# attinytrafficlight.net
KiCad netlist of a schematic drawn in EAGLE
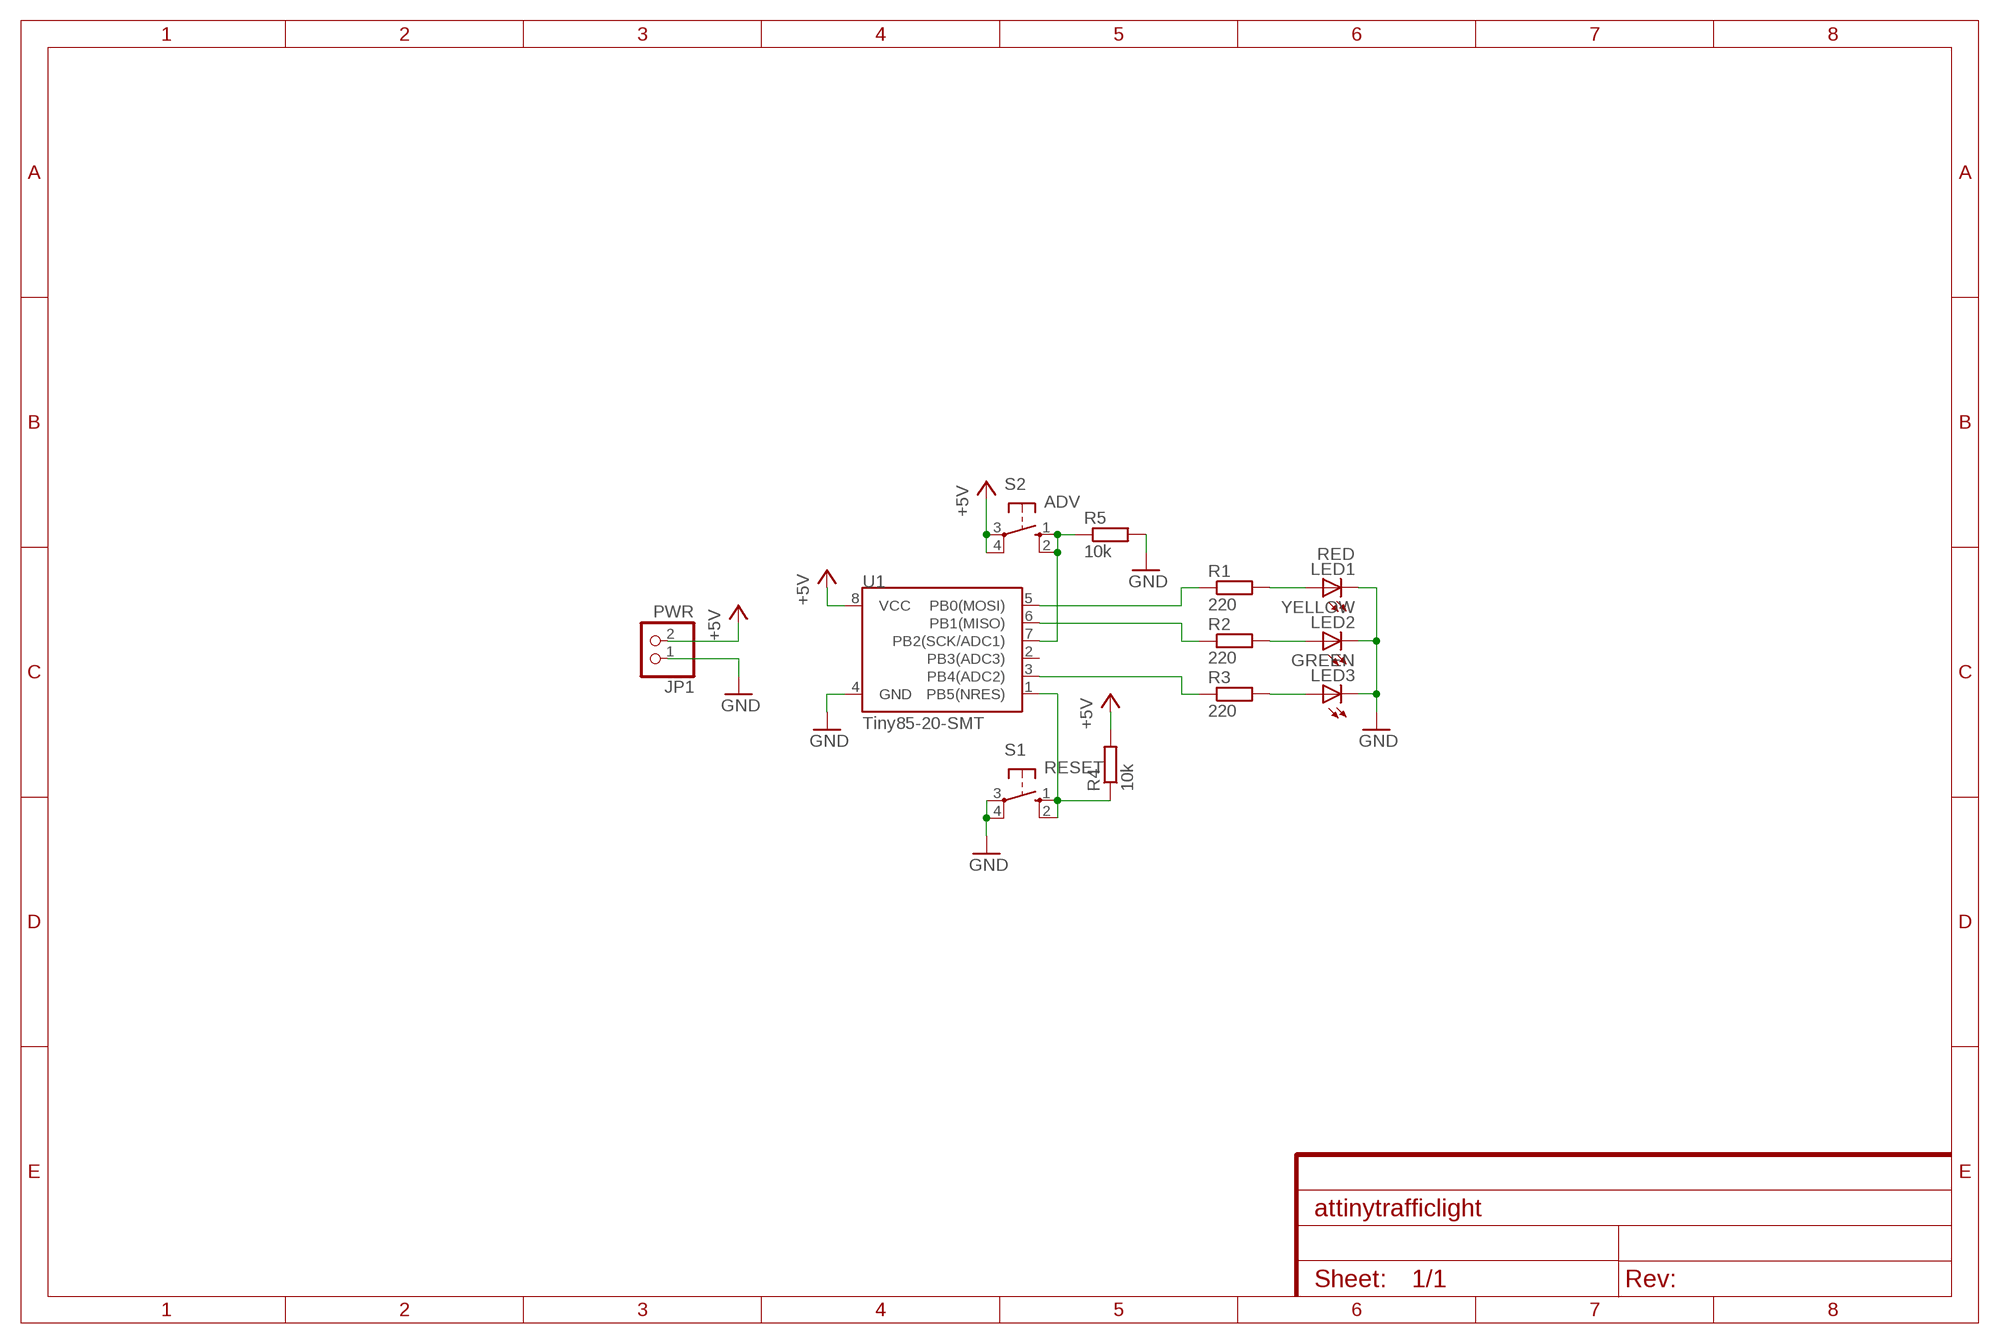
[diagram p0: schematic, sheet 1]

(export (version "E")
  (design (tool "Eeschema 10.0.6"))
  (components
    (comp (ref "JP1")
      (value "PWR")
      (footprint "eagle-import:1X02")
      (libsource (lib "eagle-import") (part "PINHD-1X2"))
    )
    (comp (ref "LED1")
      (value "RED")
      (footprint "eagle-import:SML0805")
      (libsource (lib "eagle-import") (part "LEDSML0805"))
    )
    (comp (ref "LED2")
      (value "YELLOW")
      (footprint "eagle-import:SML0805")
      (libsource (lib "eagle-import") (part "LEDSML0805"))
    )
    (comp (ref "LED3")
      (value "GREEN")
      (footprint "eagle-import:SML0805")
      (libsource (lib "eagle-import") (part "LEDSML0805"))
    )
    (comp (ref "R1")
      (value "220")
      (footprint "eagle-import:R0805")
      (libsource (lib "eagle-import") (part "R-EU_R0805"))
    )
    (comp (ref "R2")
      (value "220")
      (footprint "eagle-import:R0805")
      (libsource (lib "eagle-import") (part "R-EU_R0805"))
    )
    (comp (ref "R3")
      (value "220")
      (footprint "eagle-import:R0805")
      (libsource (lib "eagle-import") (part "R-EU_R0805"))
    )
    (comp (ref "R4")
      (value "10k")
      (footprint "eagle-import:R0805")
      (libsource (lib "eagle-import") (part "R-EU_R0805"))
    )
    (comp (ref "R5")
      (value "10k")
      (footprint "eagle-import:R0805")
      (libsource (lib "eagle-import") (part "R-EU_R0805"))
    )
    (comp (ref "S1")
      (value "RESET")
      (footprint "eagle-import:B3F-10XX")
      (fields (field (name "MPN") "B3F-1000"))
      (libsource (lib "eagle-import") (part "10-XX"))
    )
    (comp (ref "S2")
      (value "ADV")
      (footprint "eagle-import:B3F-10XX")
      (fields (field (name "MPN") "B3F-1000"))
      (libsource (lib "eagle-import") (part "10-XX"))
    )
    (comp (ref "U1")
      (value "Tiny85-20-SMT")
      (footprint "eagle-import:SO08-EIAJ")
      (libsource (lib "eagle-import") (part "ATTINY45TINY85-20-SMT"))
    )
  )
  (nets
    (net (code "1") (name "+5V") (class "Default")
      (node (ref "JP1") (pin "2") (pinfunction "2_2") (pintype "passive"))
      (node (ref "R4") (pin "2") (pinfunction "2_2") (pintype "passive"))
      (node (ref "S2") (pin "3") (pinfunction "P_3") (pintype "passive"))
      (node (ref "S2") (pin "4") (pinfunction "P1_4") (pintype "passive"))
      (node (ref "U1") (pin "8") (pinfunction "VCC_8") (pintype "bidirectional"))
    )
    (net (code "2") (name "GND") (class "Default")
      (node (ref "JP1") (pin "1") (pinfunction "1_1") (pintype "passive"))
      (node (ref "LED1") (pin "C") (pinfunction "C_C") (pintype "passive"))
      (node (ref "LED2") (pin "C") (pinfunction "C_C") (pintype "passive"))
      (node (ref "LED3") (pin "C") (pinfunction "C_C") (pintype "passive"))
      (node (ref "R5") (pin "2") (pinfunction "2_2") (pintype "passive"))
      (node (ref "S1") (pin "3") (pinfunction "P_3") (pintype "passive"))
      (node (ref "S1") (pin "4") (pinfunction "P1_4") (pintype "passive"))
      (node (ref "U1") (pin "4") (pinfunction "GND_4") (pintype "bidirectional"))
    )
    (net (code "3") (name "Net-(LED1-PadA)") (class "Default")
      (node (ref "LED1") (pin "A") (pinfunction "A_A") (pintype "passive"))
      (node (ref "R1") (pin "2") (pinfunction "2_2") (pintype "passive"))
    )
    (net (code "4") (name "Net-(LED2-PadA)") (class "Default")
      (node (ref "LED2") (pin "A") (pinfunction "A_A") (pintype "passive"))
      (node (ref "R2") (pin "2") (pinfunction "2_2") (pintype "passive"))
    )
    (net (code "5") (name "Net-(LED3-PadA)") (class "Default")
      (node (ref "LED3") (pin "A") (pinfunction "A_A") (pintype "passive"))
      (node (ref "R3") (pin "2") (pinfunction "2_2") (pintype "passive"))
    )
    (net (code "6") (name "Net-(S1-S)") (class "Default")
      (node (ref "R4") (pin "1") (pinfunction "1_1") (pintype "passive"))
      (node (ref "S1") (pin "1") (pinfunction "S_1") (pintype "passive"))
      (node (ref "S1") (pin "2") (pinfunction "S1_2") (pintype "passive"))
      (node (ref "U1") (pin "1") (pinfunction "PB5(NRES)_1") (pintype "bidirectional"))
    )
    (net (code "7") (name "Net-(S2-S)") (class "Default")
      (node (ref "R5") (pin "1") (pinfunction "1_1") (pintype "passive"))
      (node (ref "S2") (pin "1") (pinfunction "S_1") (pintype "passive"))
      (node (ref "S2") (pin "2") (pinfunction "S1_2") (pintype "passive"))
      (node (ref "U1") (pin "7") (pinfunction "PB2(SCK/ADC1)_7") (pintype "bidirectional"))
    )
    (net (code "8") (name "Net-(U1-PB0(MOSI))") (class "Default")
      (node (ref "R1") (pin "1") (pinfunction "1_1") (pintype "passive"))
      (node (ref "U1") (pin "5") (pinfunction "PB0(MOSI)_5") (pintype "bidirectional"))
    )
    (net (code "9") (name "Net-(U1-PB1(MISO))") (class "Default")
      (node (ref "R2") (pin "1") (pinfunction "1_1") (pintype "passive"))
      (node (ref "U1") (pin "6") (pinfunction "PB1(MISO)_6") (pintype "bidirectional"))
    )
    (net (code "10") (name "Net-(U1-PB4(ADC2))") (class "Default")
      (node (ref "R3") (pin "1") (pinfunction "1_1") (pintype "passive"))
      (node (ref "U1") (pin "3") (pinfunction "PB4(ADC2)_3") (pintype "bidirectional"))
    )
    (net (code "11") (name "unconnected-(U1-PB3(ADC3)-Pad2)") (class "Default")
      (node (ref "U1") (pin "2") (pinfunction "PB3(ADC3)_2") (pintype "bidirectional"))
    )
  )
)
